# ranback_all.net
KiCad netlist of a schematic drawn in EAGLE
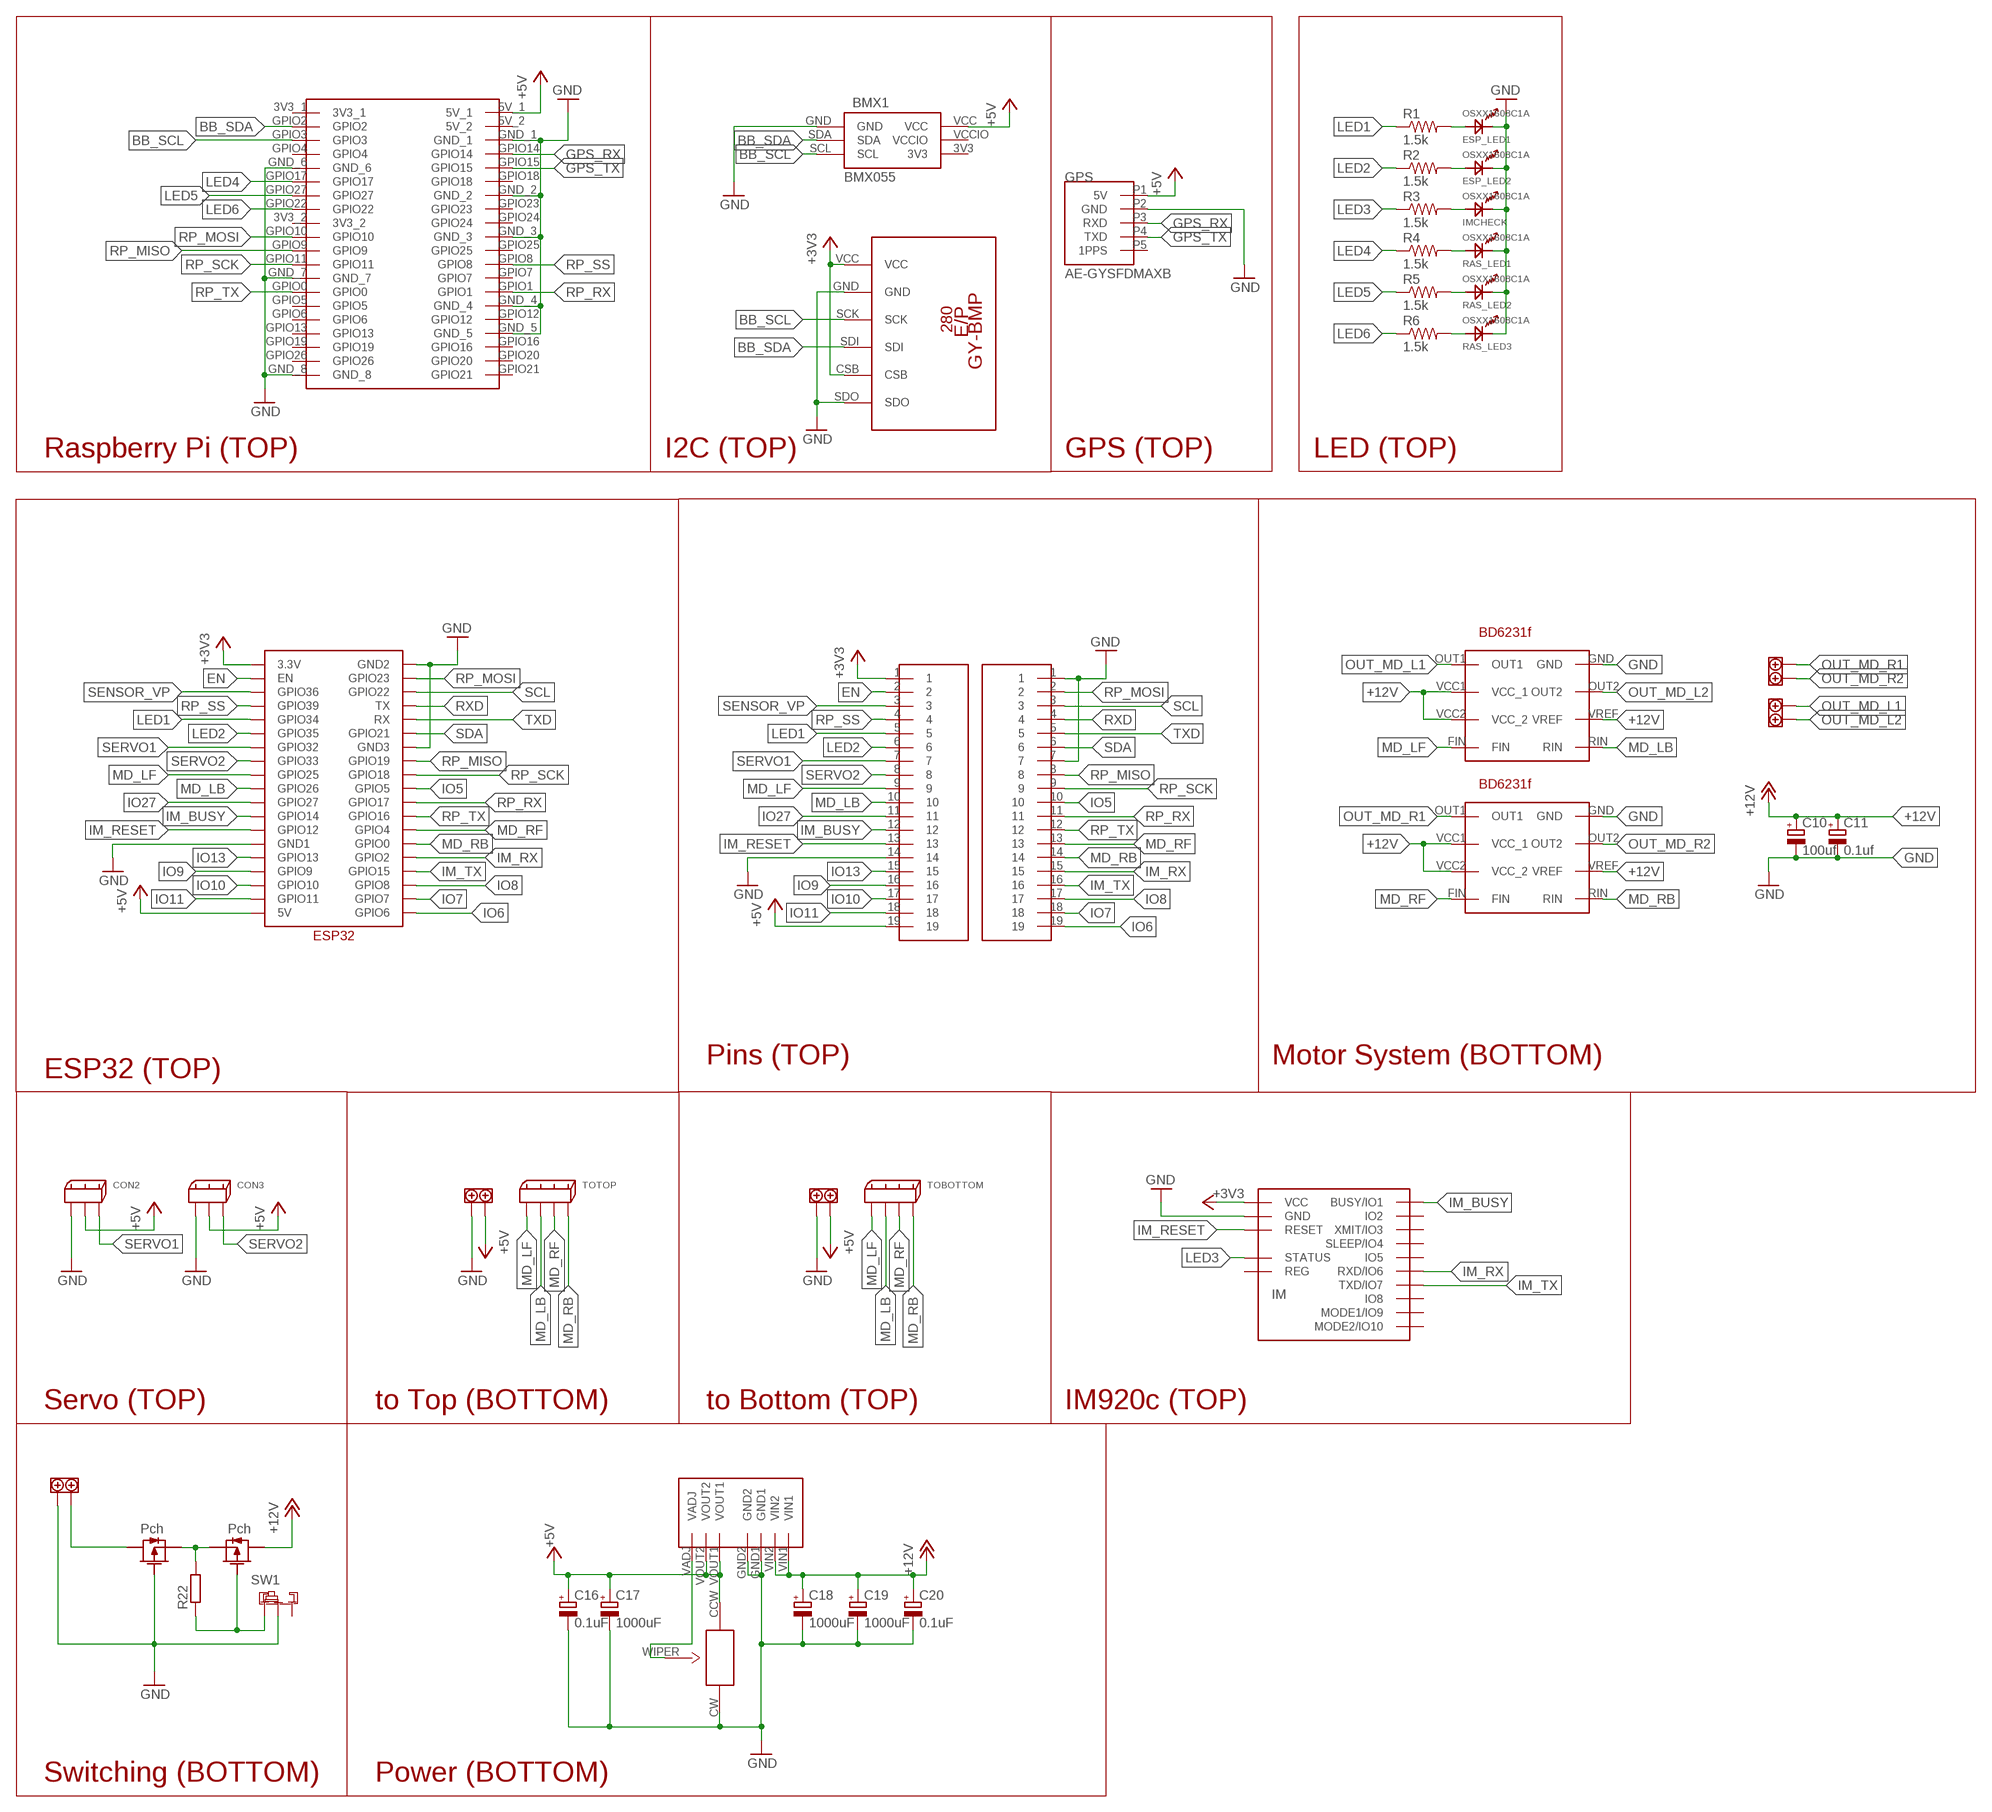
[diagram p0: schematic, sheet 1]

(export (version "E")
  (design (tool "Eeschema 10.0.6"))
  (components
    (comp (ref "100KR1")
      (value "100kR")
      (footprint "eagle-import:3362P")
      (libsource (lib "eagle-import") (part "3362P"))
    )
    (comp (ref "BMX1")
      (value "BMX055")
      (footprint "eagle-import:BMX055")
      (libsource (lib "eagle-import") (part "BMX055"))
    )
    (comp (ref "C10")
      (value "100uf")
      (footprint "eagle-import:E2,5-7")
      (libsource (lib "eagle-import") (part "CPOL-EUE2.5-7"))
    )
    (comp (ref "C11")
      (value "0.1uf")
      (footprint "eagle-import:E2,5-7")
      (libsource (lib "eagle-import") (part "CPOL-EUE2.5-7"))
    )
    (comp (ref "C16")
      (value "0.1uF")
      (footprint "eagle-import:E2,5-7")
      (libsource (lib "eagle-import") (part "CPOL-EUE2.5-7"))
    )
    (comp (ref "C17")
      (value "1000uF")
      (footprint "eagle-import:E5-10,5")
      (libsource (lib "eagle-import") (part "CPOL-EUE5-10.5"))
    )
    (comp (ref "C18")
      (value "1000uF")
      (footprint "eagle-import:E5-10,5")
      (libsource (lib "eagle-import") (part "CPOL-EUE5-10.5"))
    )
    (comp (ref "C19")
      (value "1000uF")
      (footprint "eagle-import:E5-10,5")
      (libsource (lib "eagle-import") (part "CPOL-EUE5-10.5"))
    )
    (comp (ref "C20")
      (value "0.1uF")
      (footprint "eagle-import:E2,5-7")
      (libsource (lib "eagle-import") (part "CPOL-EUE2.5-7"))
    )
    (comp (ref "CON2")
      (value "2.5_MINI-SPOX_3PIN")
      (footprint "eagle-import:2.5_MINI-SPOX_3PIN")
      (libsource (lib "eagle-import") (part "2.5_MINI-SPOX_3PIN"))
    )
    (comp (ref "CON3")
      (value "2.5_MINI-SPOX_3PIN")
      (footprint "eagle-import:2.5_MINI-SPOX_3PIN")
      (libsource (lib "eagle-import") (part "2.5_MINI-SPOX_3PIN"))
    )
    (comp (ref "ESP_LED1")
      (value "OSXX1608C1A")
      (footprint "eagle-import:OSXX1608C1A")
      (libsource (lib "eagle-import") (part "OSXX1608C1A"))
    )
    (comp (ref "ESP_LED2")
      (value "OSXX1608C1A")
      (footprint "eagle-import:OSXX1608C1A")
      (libsource (lib "eagle-import") (part "OSXX1608C1A"))
    )
    (comp (ref "GPS")
      (value "AE-GYSFDMAXB")
      (footprint "eagle-import:AE-GYSFDMAXB")
      (libsource (lib "eagle-import") (part "AE-GYSFDMAXB"))
    )
    (comp (ref "IM")
      (value "IM920C")
      (footprint "eagle-import:IM920C")
      (libsource (lib "eagle-import") (part "IM920C"))
    )
    (comp (ref "IMCHECK")
      (value "OSXX1608C1A")
      (footprint "eagle-import:OSXX1608C1A")
      (libsource (lib "eagle-import") (part "OSXX1608C1A"))
    )
    (comp (ref "MD_L")
      (value "BD6231F")
      (footprint "eagle-import:BD6231F")
      (libsource (lib "eagle-import") (part "BD6231F"))
    )
    (comp (ref "MD_R")
      (value "BD6231F")
      (footprint "eagle-import:BD6231F")
      (libsource (lib "eagle-import") (part "BD6231F"))
    )
    (comp (ref "PIN_L")
      (value "19_2.54")
      (footprint "eagle-import:19_2.54")
      (libsource (lib "eagle-import") (part "19_2.54"))
    )
    (comp (ref "PIN_R")
      (value "19_2.54")
      (footprint "eagle-import:19_2.54")
      (libsource (lib "eagle-import") (part "19_2.54"))
    )
    (comp (ref "R1")
      (value "1.5k")
      (footprint "eagle-import:R0603")
      (libsource (lib "eagle-import") (part "R-US_R0603"))
    )
    (comp (ref "R2")
      (value "1.5k")
      (footprint "eagle-import:R0603")
      (libsource (lib "eagle-import") (part "R-US_R0603"))
    )
    (comp (ref "R3")
      (value "1.5k")
      (footprint "eagle-import:R0603")
      (libsource (lib "eagle-import") (part "R-US_R0603"))
    )
    (comp (ref "R4")
      (value "1.5k")
      (footprint "eagle-import:R0603")
      (libsource (lib "eagle-import") (part "R-US_R0603"))
    )
    (comp (ref "R5")
      (value "1.5k")
      (footprint "eagle-import:R0603")
      (libsource (lib "eagle-import") (part "R-US_R0603"))
    )
    (comp (ref "R6")
      (value "1.5k")
      (footprint "eagle-import:R0603")
      (libsource (lib "eagle-import") (part "R-US_R0603"))
    )
    (comp (ref "R22")
      (value "R-EU_0207/10")
      (footprint "eagle-import:0207_10")
      (libsource (lib "eagle-import") (part "R-EU_0207/10"))
    )
    (comp (ref "RASPBERRYPI_4B")
      (value "RASPBERRYPI4B")
      (footprint "eagle-import:RASPBERRYPI4B")
      (libsource (lib "eagle-import") (part "RASPBERRYPI4B"))
    )
    (comp (ref "RAS_LED1")
      (value "OSXX1608C1A")
      (footprint "eagle-import:OSXX1608C1A")
      (libsource (lib "eagle-import") (part "OSXX1608C1A"))
    )
    (comp (ref "RAS_LED2")
      (value "OSXX1608C1A")
      (footprint "eagle-import:OSXX1608C1A")
      (libsource (lib "eagle-import") (part "OSXX1608C1A"))
    )
    (comp (ref "RAS_LED3")
      (value "OSXX1608C1A")
      (footprint "eagle-import:OSXX1608C1A")
      (libsource (lib "eagle-import") (part "OSXX1608C1A"))
    )
    (comp (ref "SW1")
      (value "SRIDE_SWITCH")
      (footprint "eagle-import:SRIDE_SWITCH")
      (libsource (lib "eagle-import") (part "SRIDE_SWITCH"))
    )
    (comp (ref "TM1")
      (value "TERMINAL_SLOPED_2PIN")
      (footprint "eagle-import:TERMINAL_SLOPED_2PIN")
      (libsource (lib "eagle-import") (part "TERMINAL_SLOPED_2PIN"))
    )
    (comp (ref "TM2")
      (value "TERMINAL_SLOPED_2PIN")
      (footprint "eagle-import:TERMINAL_SLOPED_2PIN")
      (libsource (lib "eagle-import") (part "TERMINAL_SLOPED_2PIN"))
    )
    (comp (ref "TM3")
      (value "TERMINAL_SLOPED_2PIN")
      (footprint "eagle-import:TERMINAL_SLOPED_2PIN")
      (libsource (lib "eagle-import") (part "TERMINAL_SLOPED_2PIN"))
    )
    (comp (ref "TM4")
      (value "TERMINAL_SLOPED_2PIN")
      (footprint "eagle-import:TERMINAL_SLOPED_2PIN")
      (libsource (lib "eagle-import") (part "TERMINAL_SLOPED_2PIN"))
    )
    (comp (ref "TM5")
      (value "TERMINAL_SLOPED_2PIN")
      (footprint "eagle-import:TERMINAL_SLOPED_2PIN")
      (libsource (lib "eagle-import") (part "TERMINAL_SLOPED_2PIN"))
    )
    (comp (ref "TOBOTTOM")
      (value "2.5_MINI-SPOX_4PIN")
      (footprint "eagle-import:2.5_MINI-SPOX_4PIN")
      (libsource (lib "eagle-import") (part "2.5_MINI-SPOX_4PIN"))
    )
    (comp (ref "TOTOP")
      (value "2.5_MINI-SPOX_4PIN")
      (footprint "eagle-import:2.5_MINI-SPOX_4PIN")
      (libsource (lib "eagle-import") (part "2.5_MINI-SPOX_4PIN"))
    )
    (comp (ref "U$2")
      (value "ESP32")
      (footprint "eagle-import:ESP32")
      (libsource (lib "eagle-import") (part "ESP32"))
    )
    (comp (ref "U$7")
      (value "2SJ681-PCH")
      (footprint "eagle-import:2SJ681")
      (libsource (lib "eagle-import") (part "2SJ681-PCH"))
    )
    (comp (ref "U$8")
      (value "5V3A_KIC-053")
      (footprint "eagle-import:5V3A_KIC-053")
      (libsource (lib "eagle-import") (part "5V3A_KIC-053"))
    )
    (comp (ref "U$9")
      (value "GY-BPM280")
      (footprint "eagle-import:GY-BMP280-FOOTPRINT")
      (libsource (lib "eagle-import") (part "GY-BPM280"))
    )
    (comp (ref "U$10")
      (value "2SJ681-PCH")
      (footprint "eagle-import:2SJ681")
      (libsource (lib "eagle-import") (part "2SJ681-PCH"))
    )
  )
  (nets
    (net (code "1") (name "+3V3") (class "Default")
      (node (ref "IM") (pin "$P17") (pinfunction "VCC_$P17") (pintype "bidirectional"))
      (node (ref "PIN_L") (pin "1") (pinfunction "1_1") (pintype "bidirectional"))
      (node (ref "U$2") (pin "3.3V") (pinfunction "3.3V_3.3V") (pintype "bidirectional"))
      (node (ref "U$9") (pin "CSB") (pinfunction "CSB_CSB") (pintype "bidirectional"))
      (node (ref "U$9") (pin "VCC") (pinfunction "VCC_VCC") (pintype "bidirectional"))
    )
    (net (code "2") (name "+5V") (class "Default")
      (node (ref "100KR1") (pin "CCW") (pinfunction "CCW_CCW") (pintype "bidirectional"))
      (node (ref "BMX1") (pin "VCC") (pinfunction "VCC_VCC") (pintype "power_in"))
      (node (ref "C16") (pin "+") (pinfunction "+_+") (pintype "passive"))
      (node (ref "C17") (pin "+") (pinfunction "+_+") (pintype "passive"))
      (node (ref "CON2") (pin "2") (pinfunction "2_2") (pintype "bidirectional"))
      (node (ref "CON3") (pin "2") (pinfunction "2_2") (pintype "bidirectional"))
      (node (ref "GPS") (pin "P1") (pinfunction "5V_P1") (pintype "bidirectional"))
      (node (ref "PIN_L") (pin "19") (pinfunction "19_19") (pintype "bidirectional"))
      (node (ref "RASPBERRYPI_4B") (pin "5V_1") (pinfunction "5V_1_5V_1") (pintype "bidirectional"))
      (node (ref "TM4") (pin "1") (pinfunction "1_1") (pintype "bidirectional"))
      (node (ref "TM5") (pin "1") (pinfunction "1_1") (pintype "bidirectional"))
      (node (ref "U$2") (pin "5V") (pinfunction "5V_5V") (pintype "bidirectional"))
      (node (ref "U$8") (pin "VOUT1") (pinfunction "VOUT1_VOUT1") (pintype "bidirectional"))
      (node (ref "U$8") (pin "VOUT2") (pinfunction "VOUT2_VOUT2") (pintype "bidirectional"))
    )
    (net (code "3") (name "+12V") (class "Default")
      (node (ref "C10") (pin "+") (pinfunction "+_+") (pintype "passive"))
      (node (ref "C11") (pin "+") (pinfunction "+_+") (pintype "passive"))
      (node (ref "C18") (pin "+") (pinfunction "+_+") (pintype "passive"))
      (node (ref "C19") (pin "+") (pinfunction "+_+") (pintype "passive"))
      (node (ref "C20") (pin "+") (pinfunction "+_+") (pintype "passive"))
      (node (ref "MD_L") (pin "VCC1") (pinfunction "VCC_1_VCC1") (pintype "bidirectional"))
      (node (ref "MD_L") (pin "VCC2") (pinfunction "VCC_2_VCC2") (pintype "bidirectional"))
      (node (ref "MD_L") (pin "VREF") (pinfunction "VREF_VREF") (pintype "bidirectional"))
      (node (ref "MD_R") (pin "VCC1") (pinfunction "VCC_1_VCC1") (pintype "bidirectional"))
      (node (ref "MD_R") (pin "VCC2") (pinfunction "VCC_2_VCC2") (pintype "bidirectional"))
      (node (ref "MD_R") (pin "VREF") (pinfunction "VREF_VREF") (pintype "bidirectional"))
      (node (ref "U$10") (pin "DRAIN") (pinfunction "DRAIN_DRAIN") (pintype "bidirectional"))
      (node (ref "U$8") (pin "VIN1") (pinfunction "VIN1_VIN1") (pintype "bidirectional"))
      (node (ref "U$8") (pin "VIN2") (pinfunction "VIN2_VIN2") (pintype "bidirectional"))
    )
    (net (code "4") (name "/3V3") (class "Default")
      (node (ref "BMX1") (pin "3V3") (pinfunction "3V3_3V3") (pintype "power_in"))
    )
    (net (code "5") (name "/VCCIO") (class "Default")
      (node (ref "BMX1") (pin "VCCIO") (pinfunction "VCCIO_VCCIO") (pintype "power_in"))
    )
    (net (code "6") (name "BB_SCL") (class "Default")
      (node (ref "BMX1") (pin "SCL") (pinfunction "SCL_SCL") (pintype "bidirectional"))
      (node (ref "RASPBERRYPI_4B") (pin "GPIO3") (pinfunction "GPIO3_GPIO3") (pintype "bidirectional"))
      (node (ref "U$9") (pin "SCK") (pinfunction "SCK_SCK") (pintype "bidirectional"))
    )
    (net (code "7") (name "BB_SDA") (class "Default")
      (node (ref "BMX1") (pin "SDA") (pinfunction "SDA_SDA") (pintype "bidirectional"))
      (node (ref "RASPBERRYPI_4B") (pin "GPIO2") (pinfunction "GPIO2_GPIO2") (pintype "bidirectional"))
      (node (ref "U$9") (pin "SDI") (pinfunction "SDI_SDI") (pintype "bidirectional"))
    )
    (net (code "8") (name "EN") (class "Default")
      (node (ref "PIN_L") (pin "2") (pinfunction "2_2") (pintype "bidirectional"))
      (node (ref "U$2") (pin "EN") (pinfunction "EN_EN") (pintype "bidirectional"))
    )
    (net (code "9") (name "GND") (class "Default")
      (node (ref "100KR1") (pin "CW") (pinfunction "CW_CW") (pintype "bidirectional"))
      (node (ref "BMX1") (pin "GND") (pinfunction "GND_GND") (pintype "power_in"))
      (node (ref "C10") (pin "-") (pinfunction "-_-") (pintype "passive"))
      (node (ref "C11") (pin "-") (pinfunction "-_-") (pintype "passive"))
      (node (ref "C16") (pin "-") (pinfunction "-_-") (pintype "passive"))
      (node (ref "C17") (pin "-") (pinfunction "-_-") (pintype "passive"))
      (node (ref "C18") (pin "-") (pinfunction "-_-") (pintype "passive"))
      (node (ref "C19") (pin "-") (pinfunction "-_-") (pintype "passive"))
      (node (ref "C20") (pin "-") (pinfunction "-_-") (pintype "passive"))
      (node (ref "CON2") (pin "1") (pinfunction "1_1") (pintype "bidirectional"))
      (node (ref "CON3") (pin "1") (pinfunction "1_1") (pintype "bidirectional"))
      (node (ref "ESP_LED1") (pin "CT") (pinfunction "CT_CT") (pintype "bidirectional"))
      (node (ref "ESP_LED2") (pin "CT") (pinfunction "CT_CT") (pintype "bidirectional"))
      (node (ref "GPS") (pin "P2") (pinfunction "GND_P2") (pintype "bidirectional"))
      (node (ref "IM") (pin "$P18") (pinfunction "GND_$P18") (pintype "bidirectional"))
      (node (ref "IMCHECK") (pin "CT") (pinfunction "CT_CT") (pintype "bidirectional"))
      (node (ref "MD_L") (pin "GND") (pinfunction "GND_GND") (pintype "bidirectional"))
      (node (ref "MD_R") (pin "GND") (pinfunction "GND_GND") (pintype "bidirectional"))
      (node (ref "PIN_L") (pin "14") (pinfunction "14_14") (pintype "bidirectional"))
      (node (ref "PIN_R") (pin "1") (pinfunction "1_1") (pintype "bidirectional"))
      (node (ref "PIN_R") (pin "7") (pinfunction "7_7") (pintype "bidirectional"))
      (node (ref "RASPBERRYPI_4B") (pin "GND_1") (pinfunction "GND_1_GND_1") (pintype "bidirectional"))
      (node (ref "RASPBERRYPI_4B") (pin "GND_2") (pinfunction "GND_2_GND_2") (pintype "bidirectional"))
      (node (ref "RASPBERRYPI_4B") (pin "GND_3") (pinfunction "GND_3_GND_3") (pintype "bidirectional"))
      (node (ref "RASPBERRYPI_4B") (pin "GND_4") (pinfunction "GND_4_GND_4") (pintype "bidirectional"))
      (node (ref "RASPBERRYPI_4B") (pin "GND_5") (pinfunction "GND_5_GND_5") (pintype "bidirectional"))
      (node (ref "RASPBERRYPI_4B") (pin "GND_6") (pinfunction "GND_6_GND_6") (pintype "bidirectional"))
      (node (ref "RASPBERRYPI_4B") (pin "GND_7") (pinfunction "GND_7_GND_7") (pintype "bidirectional"))
      (node (ref "RASPBERRYPI_4B") (pin "GND_8") (pinfunction "GND_8_GND_8") (pintype "bidirectional"))
      (node (ref "RAS_LED1") (pin "CT") (pinfunction "CT_CT") (pintype "bidirectional"))
      (node (ref "RAS_LED2") (pin "CT") (pinfunction "CT_CT") (pintype "bidirectional"))
      (node (ref "RAS_LED3") (pin "CT") (pinfunction "CT_CT") (pintype "bidirectional"))
      (node (ref "SW1") (pin "LR") (pinfunction "LR_LR") (pintype "bidirectional"))
      (node (ref "TM3") (pin "2") (pinfunction "2_2") (pintype "bidirectional"))
      (node (ref "TM4") (pin "2") (pinfunction "2_2") (pintype "bidirectional"))
      (node (ref "TM5") (pin "2") (pinfunction "2_2") (pintype "bidirectional"))
      (node (ref "U$2") (pin "GND1") (pinfunction "GND1_GND1") (pintype "bidirectional"))
      (node (ref "U$2") (pin "GND2") (pinfunction "GND2_GND2") (pintype "bidirectional"))
      (node (ref "U$2") (pin "GND3") (pinfunction "GND3_GND3") (pintype "bidirectional"))
      (node (ref "U$7") (pin "GATE") (pinfunction "GATE_GATE") (pintype "bidirectional"))
      (node (ref "U$8") (pin "GND1") (pinfunction "GND1_GND1") (pintype "bidirectional"))
      (node (ref "U$8") (pin "GND2") (pinfunction "GND2_GND2") (pintype "bidirectional"))
      (node (ref "U$9") (pin "GND") (pinfunction "GND_GND") (pintype "bidirectional"))
      (node (ref "U$9") (pin "SDO") (pinfunction "SDO_SDO") (pintype "bidirectional"))
    )
    (net (code "10") (name "GPS_RX") (class "Default")
      (node (ref "GPS") (pin "P3") (pinfunction "RXD_P3") (pintype "bidirectional"))
      (node (ref "RASPBERRYPI_4B") (pin "GPIO14") (pinfunction "GPIO14_GPIO14") (pintype "bidirectional"))
    )
    (net (code "11") (name "GPS_TX") (class "Default")
      (node (ref "GPS") (pin "P4") (pinfunction "TXD_P4") (pintype "bidirectional"))
      (node (ref "RASPBERRYPI_4B") (pin "GPIO15") (pinfunction "GPIO15_GPIO15") (pintype "bidirectional"))
    )
    (net (code "12") (name "IM_BUSY") (class "Default")
      (node (ref "IM") (pin "$P1") (pinfunction "BUSY/IO1_$P1") (pintype "bidirectional"))
      (node (ref "PIN_L") (pin "12") (pinfunction "12_12") (pintype "bidirectional"))
      (node (ref "U$2") (pin "GPIO14") (pinfunction "GPIO14_GPIO14") (pintype "bidirectional"))
    )
    (net (code "13") (name "IM_RESET") (class "Default")
      (node (ref "IM") (pin "$P19") (pinfunction "RESET_$P19") (pintype "bidirectional"))
      (node (ref "PIN_L") (pin "13") (pinfunction "13_13") (pintype "bidirectional"))
      (node (ref "U$2") (pin "GPIO12") (pinfunction "GPIO12_GPIO12") (pintype "bidirectional"))
    )
    (net (code "14") (name "IM_RX") (class "Default")
      (node (ref "IM") (pin "$P6") (pinfunction "RXD/IO6_$P6") (pintype "bidirectional"))
      (node (ref "PIN_R") (pin "15") (pinfunction "15_15") (pintype "bidirectional"))
      (node (ref "U$2") (pin "GPIO2") (pinfunction "GPIO2_GPIO2") (pintype "bidirectional"))
    )
    (net (code "15") (name "IM_TX") (class "Default")
      (node (ref "IM") (pin "$P7") (pinfunction "TXD/IO7_$P7") (pintype "bidirectional"))
      (node (ref "PIN_R") (pin "16") (pinfunction "16_16") (pintype "bidirectional"))
      (node (ref "U$2") (pin "GPIO15") (pinfunction "GPIO15_GPIO15") (pintype "bidirectional"))
    )
    (net (code "16") (name "IO5") (class "Default")
      (node (ref "PIN_R") (pin "10") (pinfunction "10_10") (pintype "bidirectional"))
      (node (ref "U$2") (pin "GPIO5") (pinfunction "GPIO5_GPIO5") (pintype "bidirectional"))
    )
    (net (code "17") (name "IO6") (class "Default")
      (node (ref "PIN_R") (pin "19") (pinfunction "19_19") (pintype "bidirectional"))
      (node (ref "U$2") (pin "GPIO6") (pinfunction "GPIO6_GPIO6") (pintype "bidirectional"))
    )
    (net (code "18") (name "IO7") (class "Default")
      (node (ref "PIN_R") (pin "18") (pinfunction "18_18") (pintype "bidirectional"))
      (node (ref "U$2") (pin "GPIO7") (pinfunction "GPIO7_GPIO7") (pintype "bidirectional"))
    )
    (net (code "19") (name "IO8") (class "Default")
      (node (ref "PIN_R") (pin "17") (pinfunction "17_17") (pintype "bidirectional"))
      (node (ref "U$2") (pin "GPIO8") (pinfunction "GPIO8_GPIO8") (pintype "bidirectional"))
    )
    (net (code "20") (name "IO9") (class "Default")
      (node (ref "PIN_L") (pin "16") (pinfunction "16_16") (pintype "bidirectional"))
      (node (ref "U$2") (pin "GPIO9") (pinfunction "GPIO9_GPIO9") (pintype "bidirectional"))
    )
    (net (code "21") (name "IO10") (class "Default")
      (node (ref "PIN_L") (pin "17") (pinfunction "17_17") (pintype "bidirectional"))
      (node (ref "U$2") (pin "GPIO10") (pinfunction "GPIO10_GPIO10") (pintype "bidirectional"))
    )
    (net (code "22") (name "IO11") (class "Default")
      (node (ref "PIN_L") (pin "18") (pinfunction "18_18") (pintype "bidirectional"))
      (node (ref "U$2") (pin "GPIO11") (pinfunction "GPIO11_GPIO11") (pintype "bidirectional"))
    )
    (net (code "23") (name "IO13") (class "Default")
      (node (ref "PIN_L") (pin "15") (pinfunction "15_15") (pintype "bidirectional"))
      (node (ref "U$2") (pin "GPIO13") (pinfunction "GPIO13_GPIO13") (pintype "bidirectional"))
    )
    (net (code "24") (name "IO27") (class "Default")
      (node (ref "PIN_L") (pin "11") (pinfunction "11_11") (pintype "bidirectional"))
      (node (ref "U$2") (pin "GPIO27") (pinfunction "GPIO27_GPIO27") (pintype "bidirectional"))
    )
    (net (code "25") (name "LED1") (class "Default")
      (node (ref "PIN_L") (pin "5") (pinfunction "5_5") (pintype "bidirectional"))
      (node (ref "R1") (pin "1") (pinfunction "1_1") (pintype "passive"))
      (node (ref "U$2") (pin "GPIO34") (pinfunction "GPIO34_GPIO34") (pintype "bidirectional"))
    )
    (net (code "26") (name "LED2") (class "Default")
      (node (ref "PIN_L") (pin "6") (pinfunction "6_6") (pintype "bidirectional"))
      (node (ref "R2") (pin "1") (pinfunction "1_1") (pintype "passive"))
      (node (ref "U$2") (pin "GPIO35") (pinfunction "GPIO35_GPIO35") (pintype "bidirectional"))
    )
    (net (code "27") (name "LED3") (class "Default")
      (node (ref "IM") (pin "$P15") (pinfunction "STATUS_$P15") (pintype "bidirectional"))
      (node (ref "R3") (pin "1") (pinfunction "1_1") (pintype "passive"))
    )
    (net (code "28") (name "LED4") (class "Default")
      (node (ref "R4") (pin "1") (pinfunction "1_1") (pintype "passive"))
      (node (ref "RASPBERRYPI_4B") (pin "GPIO17") (pinfunction "GPIO17_GPIO17") (pintype "bidirectional"))
    )
    (net (code "29") (name "LED5") (class "Default")
      (node (ref "R5") (pin "1") (pinfunction "1_1") (pintype "passive"))
      (node (ref "RASPBERRYPI_4B") (pin "GPIO27") (pinfunction "GPIO27_GPIO27") (pintype "bidirectional"))
    )
    (net (code "30") (name "LED6") (class "Default")
      (node (ref "R6") (pin "1") (pinfunction "1_1") (pintype "passive"))
      (node (ref "RASPBERRYPI_4B") (pin "GPIO22") (pinfunction "GPIO22_GPIO22") (pintype "bidirectional"))
    )
    (net (code "31") (name "MD_LB") (class "Default")
      (node (ref "MD_L") (pin "RIN") (pinfunction "RIN_RIN") (pintype "bidirectional"))
      (node (ref "PIN_L") (pin "10") (pinfunction "10_10") (pintype "bidirectional"))
      (node (ref "TOBOTTOM") (pin "P$2") (pinfunction "2_P$2") (pintype "bidirectional"))
      (node (ref "TOTOP") (pin "P$2") (pinfunction "2_P$2") (pintype "bidirectional"))
      (node (ref "U$2") (pin "GPIO26") (pinfunction "GPIO26_GPIO26") (pintype "bidirectional"))
    )
    (net (code "32") (name "MD_LF") (class "Default")
      (node (ref "MD_L") (pin "FIN") (pinfunction "FIN_FIN") (pintype "bidirectional"))
      (node (ref "PIN_L") (pin "9") (pinfunction "9_9") (pintype "bidirectional"))
      (node (ref "TOBOTTOM") (pin "P$1") (pinfunction "1_P$1") (pintype "bidirectional"))
      (node (ref "TOTOP") (pin "P$1") (pinfunction "1_P$1") (pintype "bidirectional"))
      (node (ref "U$2") (pin "GPIO25") (pinfunction "GPIO25_GPIO25") (pintype "bidirectional"))
    )
    (net (code "33") (name "MD_RB") (class "Default")
      (node (ref "MD_R") (pin "RIN") (pinfunction "RIN_RIN") (pintype "bidirectional"))
      (node (ref "PIN_R") (pin "14") (pinfunction "14_14") (pintype "bidirectional"))
      (node (ref "TOBOTTOM") (pin "P$4") (pinfunction "4_P$4") (pintype "bidirectional"))
      (node (ref "TOTOP") (pin "P$4") (pinfunction "4_P$4") (pintype "bidirectional"))
      (node (ref "U$2") (pin "GPIO0") (pinfunction "GPIO0_GPIO0") (pintype "bidirectional"))
    )
    (net (code "34") (name "MD_RF") (class "Default")
      (node (ref "MD_R") (pin "FIN") (pinfunction "FIN_FIN") (pintype "bidirectional"))
      (node (ref "PIN_R") (pin "13") (pinfunction "13_13") (pintype "bidirectional"))
      (node (ref "TOBOTTOM") (pin "P$3") (pinfunction "3_P$3") (pintype "bidirectional"))
      (node (ref "TOTOP") (pin "P$3") (pinfunction "3_P$3") (pintype "bidirectional"))
      (node (ref "U$2") (pin "GPIO4") (pinfunction "GPIO4_GPIO4") (pintype "bidirectional"))
    )
    (net (code "35") (name "Net-(100KR1-PadWIPER)") (class "Default")
      (node (ref "100KR1") (pin "WIPER") (pinfunction "WIPER_WIPER") (pintype "bidirectional"))
      (node (ref "U$8") (pin "VADJ") (pinfunction "VADJ_VADJ") (pintype "bidirectional"))
    )
    (net (code "36") (name "Net-(ESP_LED1-PadAN)") (class "Default")
      (node (ref "ESP_LED1") (pin "AN") (pinfunction "AN_AN") (pintype "bidirectional"))
      (node (ref "R1") (pin "2") (pinfunction "2_2") (pintype "passive"))
    )
    (net (code "37") (name "Net-(ESP_LED2-PadAN)") (class "Default")
      (node (ref "ESP_LED2") (pin "AN") (pinfunction "AN_AN") (pintype "bidirectional"))
      (node (ref "R2") (pin "2") (pinfunction "2_2") (pintype "passive"))
    )
    (net (code "38") (name "Net-(IMCHECK-PadAN)") (class "Default")
      (node (ref "IMCHECK") (pin "AN") (pinfunction "AN_AN") (pintype "bidirectional"))
      (node (ref "R3") (pin "2") (pinfunction "2_2") (pintype "passive"))
    )
    (net (code "39") (name "Net-(R4-Pad2)") (class "Default")
      (node (ref "R4") (pin "2") (pinfunction "2_2") (pintype "passive"))
      (node (ref "RAS_LED1") (pin "AN") (pinfunction "AN_AN") (pintype "bidirectional"))
    )
    (net (code "40") (name "Net-(R5-Pad2)") (class "Default")
      (node (ref "R5") (pin "2") (pinfunction "2_2") (pintype "passive"))
      (node (ref "RAS_LED2") (pin "AN") (pinfunction "AN_AN") (pintype "bidirectional"))
    )
    (net (code "41") (name "Net-(R6-Pad2)") (class "Default")
      (node (ref "R6") (pin "2") (pinfunction "2_2") (pintype "passive"))
      (node (ref "RAS_LED3") (pin "AN") (pinfunction "AN_AN") (pintype "bidirectional"))
    )
    (net (code "42") (name "Net-(R22-Pad1)") (class "Default")
      (node (ref "R22") (pin "1") (pinfunction "1_1") (pintype "passive"))
      (node (ref "SW1") (pin "L") (pinfunction "L_L") (pintype "bidirectional"))
      (node (ref "U$10") (pin "GATE") (pinfunction "GATE_GATE") (pintype "bidirectional"))
    )
    (net (code "43") (name "Net-(R22-Pad2)") (class "Default")
      (node (ref "R22") (pin "2") (pinfunction "2_2") (pintype "passive"))
      (node (ref "U$10") (pin "SOURCE") (pinfunction "SOURCE_SOURCE") (pintype "bidirectional"))
      (node (ref "U$7") (pin "SOURCE") (pinfunction "SOURCE_SOURCE") (pintype "bidirectional"))
    )
    (net (code "44") (name "Net-(TM3-Pad1)") (class "Default")
      (node (ref "TM3") (pin "1") (pinfunction "1_1") (pintype "bidirectional"))
      (node (ref "U$7") (pin "DRAIN") (pinfunction "DRAIN_DRAIN") (pintype "bidirectional"))
    )
    (net (code "45") (name "OUT_MD_L1") (class "Default")
      (node (ref "MD_L") (pin "OUT1") (pinfunction "OUT1_OUT1") (pintype "bidirectional"))
      (node (ref "TM2") (pin "1") (pinfunction "1_1") (pintype "bidirectional"))
    )
    (net (code "46") (name "OUT_MD_L2") (class "Default")
      (node (ref "MD_L") (pin "OUT2") (pinfunction "OUT2_OUT2") (pintype "bidirectional"))
      (node (ref "TM2") (pin "2") (pinfunction "2_2") (pintype "bidirectional"))
    )
    (net (code "47") (name "OUT_MD_R1") (class "Default")
      (node (ref "MD_R") (pin "OUT1") (pinfunction "OUT1_OUT1") (pintype "bidirectional"))
      (node (ref "TM1") (pin "1") (pinfunction "1_1") (pintype "bidirectional"))
    )
    (net (code "48") (name "OUT_MD_R2") (class "Default")
      (node (ref "MD_R") (pin "OUT2") (pinfunction "OUT2_OUT2") (pintype "bidirectional"))
      (node (ref "TM1") (pin "2") (pinfunction "2_2") (pintype "bidirectional"))
    )
    (net (code "49") (name "RP_MISO") (class "Default")
      (node (ref "PIN_R") (pin "8") (pinfunction "8_8") (pintype "bidirectional"))
      (node (ref "RASPBERRYPI_4B") (pin "GPIO9") (pinfunction "GPIO9_GPIO9") (pintype "bidirectional"))
      (node (ref "U$2") (pin "GPIO19") (pinfunction "GPIO19_GPIO19") (pintype "bidirectional"))
    )
    (net (code "50") (name "RP_MOSI") (class "Default")
      (node (ref "PIN_R") (pin "2") (pinfunction "2_2") (pintype "bidirectional"))
      (node (ref "RASPBERRYPI_4B") (pin "GPIO10") (pinfunction "GPIO10_GPIO10") (pintype "bidirectional"))
      (node (ref "U$2") (pin "GPIO23") (pinfunction "GPIO23_GPIO23") (pintype "bidirectional"))
    )
    (net (code "51") (name "RP_RX") (class "Default")
      (node (ref "PIN_R") (pin "11") (pinfunction "11_11") (pintype "bidirectional"))
      (node (ref "RASPBERRYPI_4B") (pin "GPIO1") (pinfunction "GPIO1_GPIO1") (pintype "bidirectional"))
      (node (ref "U$2") (pin "GPIO17") (pinfunction "GPIO17_GPIO17") (pintype "bidirectional"))
    )
    (net (code "52") (name "RP_SCK") (class "Default")
      (node (ref "PIN_R") (pin "9") (pinfunction "9_9") (pintype "bidirectional"))
      (node (ref "RASPBERRYPI_4B") (pin "GPIO11") (pinfunction "GPIO11_GPIO11") (pintype "bidirectional"))
      (node (ref "U$2") (pin "GPIO18") (pinfunction "GPIO18_GPIO18") (pintype "bidirectional"))
    )
    (net (code "53") (name "RP_SS") (class "Default")
      (node (ref "PIN_L") (pin "4") (pinfunction "4_4") (pintype "bidirectional"))
      (node (ref "RASPBERRYPI_4B") (pin "GPIO8") (pinfunction "GPIO8_GPIO8") (pintype "bidirectional"))
      (node (ref "U$2") (pin "GPIO39") (pinfunction "GPIO39_GPIO39") (pintype "bidirectional"))
    )
    (net (code "54") (name "RP_TX") (class "Default")
      (node (ref "PIN_R") (pin "12") (pinfunction "12_12") (pintype "bidirectional"))
      (node (ref "RASPBERRYPI_4B") (pin "GPIO0") (pinfunction "GPIO0_GPIO0") (pintype "bidirectional"))
      (node (ref "U$2") (pin "GPIO16") (pinfunction "GPIO16_GPIO16") (pintype "bidirectional"))
    )
    (net (code "55") (name "RXD") (class "Default")
      (node (ref "PIN_R") (pin "4") (pinfunction "4_4") (pintype "bidirectional"))
      (node (ref "U$2") (pin "TX") (pinfunction "TX_TX") (pintype "bidirectional"))
    )
    (net (code "56") (name "SCL") (class "Default")
      (node (ref "PIN_R") (pin "3") (pinfunction "3_3") (pintype "bidirectional"))
      (node (ref "U$2") (pin "GPIO22") (pinfunction "GPIO22_GPIO22") (pintype "bidirectional"))
    )
    (net (code "57") (name "SDA") (class "Default")
      (node (ref "PIN_R") (pin "6") (pinfunction "6_6") (pintype "bidirectional"))
      (node (ref "U$2") (pin "GPIO21") (pinfunction "GPIO21_GPIO21") (pintype "bidirectional"))
    )
    (net (code "58") (name "SENSOR_VP") (class "Default")
      (node (ref "PIN_L") (pin "3") (pinfunction "3_3") (pintype "bidirectional"))
      (node (ref "U$2") (pin "GPIO36") (pinfunction "GPIO36_GPIO36") (pintype "bidirectional"))
    )
    (net (code "59") (name "SERVO1") (class "Default")
      (node (ref "CON2") (pin "3") (pinfunction "3_3") (pintype "bidirectional"))
      (node (ref "PIN_L") (pin "7") (pinfunction "7_7") (pintype "bidirectional"))
      (node (ref "U$2") (pin "GPIO32") (pinfunction "GPIO32_GPIO32") (pintype "bidirectional"))
    )
    (net (code "60") (name "SERVO2") (class "Default")
      (node (ref "CON3") (pin "3") (pinfunction "3_3") (pintype "bidirectional"))
      (node (ref "PIN_L") (pin "8") (pinfunction "8_8") (pintype "bidirectional"))
      (node (ref "U$2") (pin "GPIO33") (pinfunction "GPIO33_GPIO33") (pintype "bidirectional"))
    )
    (net (code "61") (name "TXD") (class "Default")
      (node (ref "PIN_R") (pin "5") (pinfunction "5_5") (pintype "bidirectional"))
      (node (ref "U$2") (pin "RX") (pinfunction "RX_RX") (pintype "bidirectional"))
    )
    (net (code "62") (name "unconnected-(GPS-1PPS-PadP5)") (class "Default")
      (node (ref "GPS") (pin "P5") (pinfunction "1PPS_P5") (pintype "bidirectional"))
    )
    (net (code "63") (name "unconnected-(IM-IO2-Pad$P2)") (class "Default")
      (node (ref "IM") (pin "$P2") (pinfunction "IO2_$P2") (pintype "bidirectional"))
    )
    (net (code "64") (name "unconnected-(IM-IO5-Pad$P5)") (class "Default")
      (node (ref "IM") (pin "$P5") (pinfunction "IO5_$P5") (pintype "bidirectional"))
    )
    (net (code "65") (name "unconnected-(IM-IO8-Pad$P8)") (class "Default")
      (node (ref "IM") (pin "$P8") (pinfunction "IO8_$P8") (pintype "bidirectional"))
    )
    (net (code "66") (name "unconnected-(IM-MODE1{slash}IO9-Pad$P9)") (class "Default")
      (node (ref "IM") (pin "$P9") (pinfunction "MODE1/IO9_$P9") (pintype "bidirectional"))
    )
    (net (code "67") (name "unconnected-(IM-MODE2{slash}IO10-Pad$P10)") (class "Default")
      (node (ref "IM") (pin "$P10") (pinfunction "MODE2/IO10_$P10") (pintype "bidirectional"))
    )
    (net (code "68") (name "unconnected-(IM-REG-Pad$P16)") (class "Default")
      (node (ref "IM") (pin "$P16") (pinfunction "REG_$P16") (pintype "bidirectional"))
    )
    (net (code "69") (name "unconnected-(IM-SLEEP{slash}IO4-Pad$P4)") (class "Default")
      (node (ref "IM") (pin "$P4") (pinfunction "SLEEP/IO4_$P4") (pintype "bidirectional"))
    )
    (net (code "70") (name "unconnected-(IM-XMIT{slash}IO3-Pad$P3)") (class "Default")
      (node (ref "IM") (pin "$P3") (pinfunction "XMIT/IO3_$P3") (pintype "bidirectional"))
    )
    (net (code "71") (name "unconnected-(RASPBERRYPI_4B-Pad3V3_1)") (class "Default")
      (node (ref "RASPBERRYPI_4B") (pin "3V3_1") (pinfunction "3V3_1_3V3_1") (pintype "bidirectional"))
    )
    (net (code "72") (name "unconnected-(RASPBERRYPI_4B-Pad3V3_2)") (class "Default")
      (node (ref "RASPBERRYPI_4B") (pin "3V3_2") (pinfunction "3V3_2_3V3_2") (pintype "bidirectional"))
    )
    (net (code "73") (name "unconnected-(RASPBERRYPI_4B-Pad5V_2)") (class "Default")
      (node (ref "RASPBERRYPI_4B") (pin "5V_2") (pinfunction "5V_2_5V_2") (pintype "bidirectional"))
    )
    (net (code "74") (name "unconnected-(RASPBERRYPI_4B-PadGPIO4)") (class "Default")
      (node (ref "RASPBERRYPI_4B") (pin "GPIO4") (pinfunction "GPIO4_GPIO4") (pintype "bidirectional"))
    )
    (net (code "75") (name "unconnected-(RASPBERRYPI_4B-PadGPIO5)") (class "Default")
      (node (ref "RASPBERRYPI_4B") (pin "GPIO5") (pinfunction "GPIO5_GPIO5") (pintype "bidirectional"))
    )
    (net (code "76") (name "unconnected-(RASPBERRYPI_4B-PadGPIO6)") (class "Default")
      (node (ref "RASPBERRYPI_4B") (pin "GPIO6") (pinfunction "GPIO6_GPIO6") (pintype "bidirectional"))
    )
    (net (code "77") (name "unconnected-(RASPBERRYPI_4B-PadGPIO7)") (class "Default")
      (node (ref "RASPBERRYPI_4B") (pin "GPIO7") (pinfunction "GPIO7_GPIO7") (pintype "bidirectional"))
    )
    (net (code "78") (name "unconnected-(RASPBERRYPI_4B-PadGPIO12)") (class "Default")
      (node (ref "RASPBERRYPI_4B") (pin "GPIO12") (pinfunction "GPIO12_GPIO12") (pintype "bidirectional"))
    )
    (net (code "79") (name "unconnected-(RASPBERRYPI_4B-PadGPIO13)") (class "Default")
      (node (ref "RASPBERRYPI_4B") (pin "GPIO13") (pinfunction "GPIO13_GPIO13") (pintype "bidirectional"))
    )
    (net (code "80") (name "unconnected-(RASPBERRYPI_4B-PadGPIO16)") (class "Default")
      (node (ref "RASPBERRYPI_4B") (pin "GPIO16") (pinfunction "GPIO16_GPIO16") (pintype "bidirectional"))
    )
    (net (code "81") (name "unconnected-(RASPBERRYPI_4B-PadGPIO18)") (class "Default")
      (node (ref "RASPBERRYPI_4B") (pin "GPIO18") (pinfunction "GPIO18_GPIO18") (pintype "bidirectional"))
    )
    (net (code "82") (name "unconnected-(RASPBERRYPI_4B-PadGPIO19)") (class "Default")
      (node (ref "RASPBERRYPI_4B") (pin "GPIO19") (pinfunction "GPIO19_GPIO19") (pintype "bidirectional"))
    )
    (net (code "83") (name "unconnected-(RASPBERRYPI_4B-PadGPIO20)") (class "Default")
      (node (ref "RASPBERRYPI_4B") (pin "GPIO20") (pinfunction "GPIO20_GPIO20") (pintype "bidirectional"))
    )
    (net (code "84") (name "unconnected-(RASPBERRYPI_4B-PadGPIO21)") (class "Default")
      (node (ref "RASPBERRYPI_4B") (pin "GPIO21") (pinfunction "GPIO21_GPIO21") (pintype "bidirectional"))
    )
    (net (code "85") (name "unconnected-(RASPBERRYPI_4B-PadGPIO23)") (class "Default")
      (node (ref "RASPBERRYPI_4B") (pin "GPIO23") (pinfunction "GPIO23_GPIO23") (pintype "bidirectional"))
    )
    (net (code "86") (name "unconnected-(RASPBERRYPI_4B-PadGPIO24)") (class "Default")
      (node (ref "RASPBERRYPI_4B") (pin "GPIO24") (pinfunction "GPIO24_GPIO24") (pintype "bidirectional"))
    )
    (net (code "87") (name "unconnected-(RASPBERRYPI_4B-PadGPIO25)") (class "Default")
      (node (ref "RASPBERRYPI_4B") (pin "GPIO25") (pinfunction "GPIO25_GPIO25") (pintype "bidirectional"))
    )
    (net (code "88") (name "unconnected-(RASPBERRYPI_4B-PadGPIO26)") (class "Default")
      (node (ref "RASPBERRYPI_4B") (pin "GPIO26") (pinfunction "GPIO26_GPIO26") (pintype "bidirectional"))
    )
    (net (code "89") (name "unconnected-(SW1-PadR)") (class "Default")
      (node (ref "SW1") (pin "R") (pinfunction "R_R") (pintype "bidirectional"))
    )
  )
)
